# Schemat.net
KiCad netlist of a schematic drawn in EAGLE
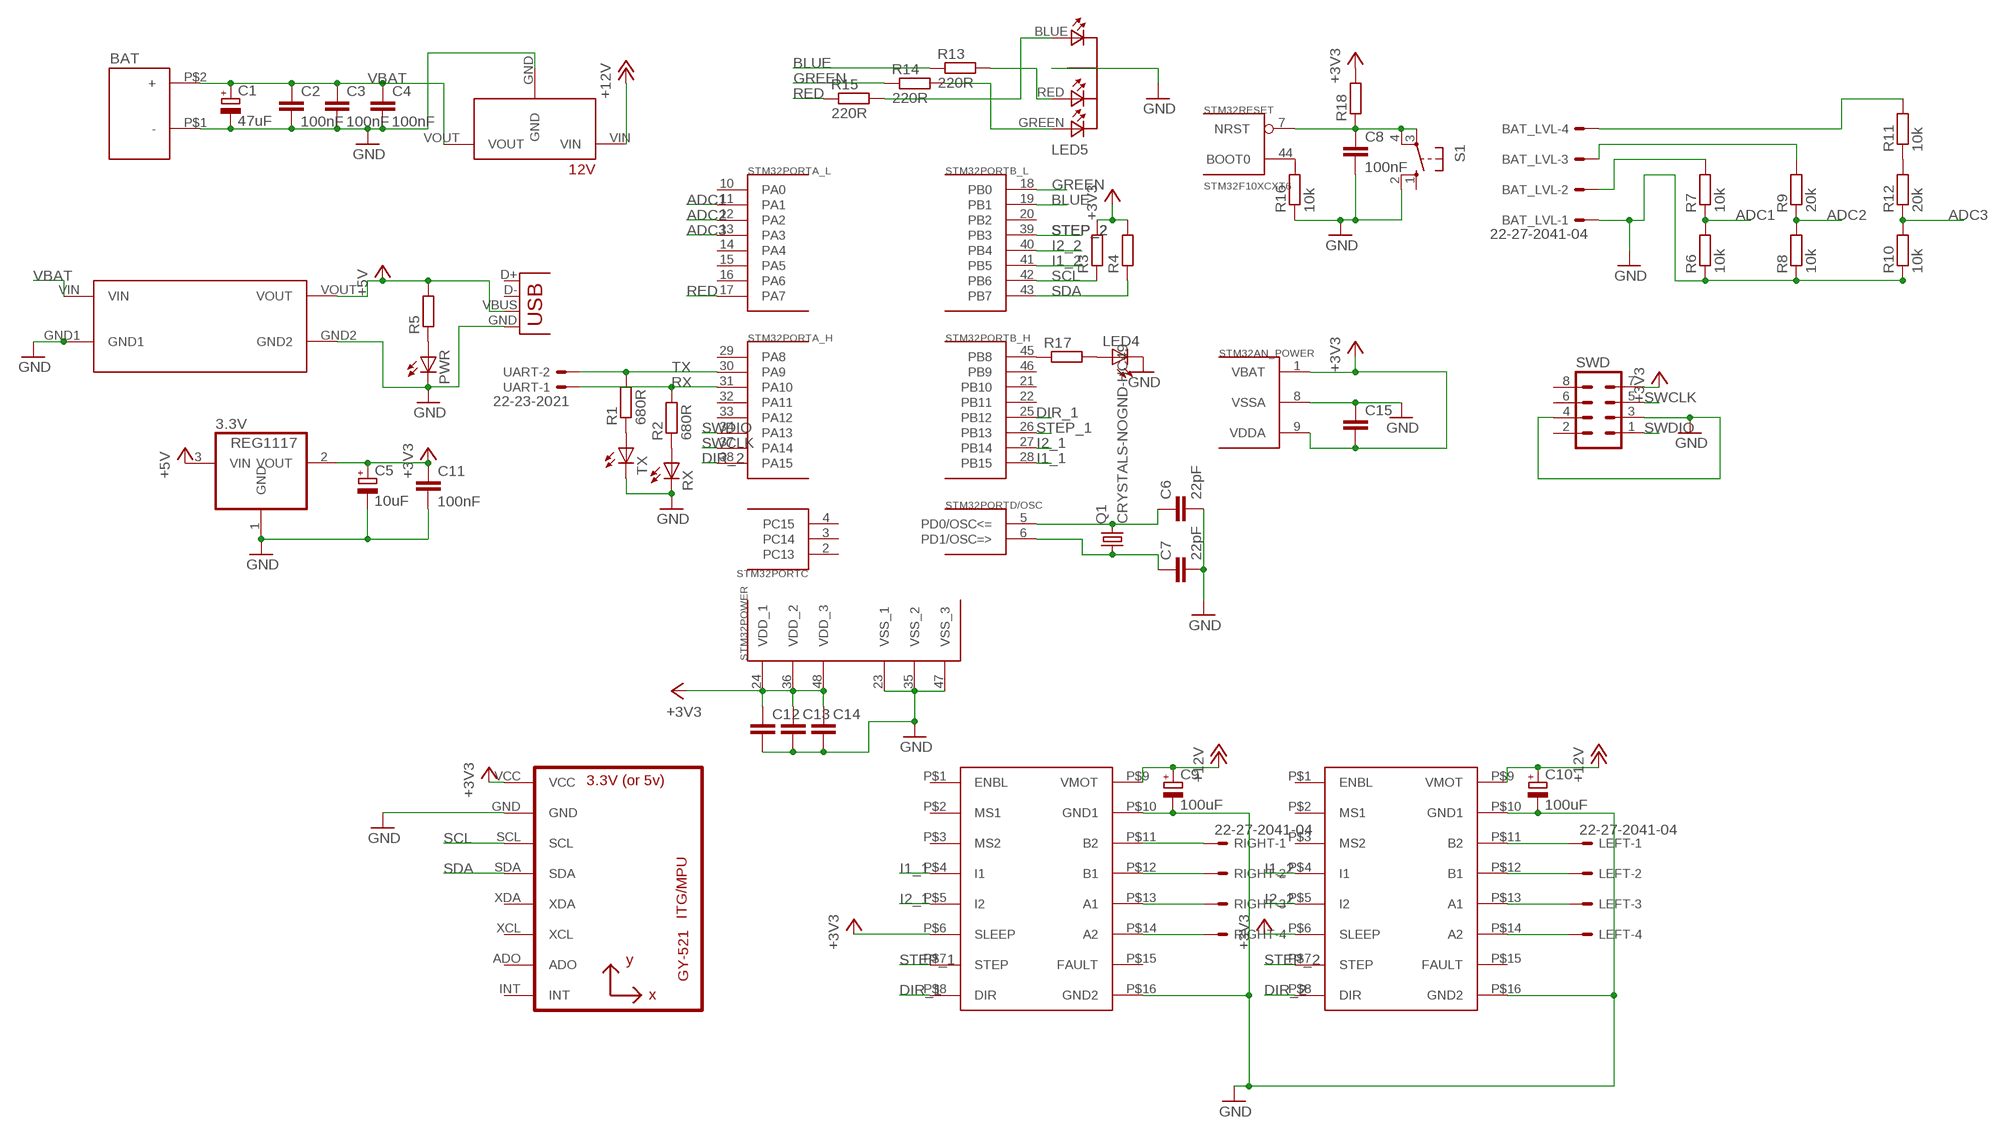
[diagram p0: schematic, sheet 1]

(export (version "E")
  (design (tool "Eeschema 10.0.6"))
  (components
    (comp (ref "3.3V")
      (value "REG1117")
      (footprint "eagle-import:SOT223")
      (libsource (lib "eagle-import") (part "REG1117"))
    )
    (comp (ref "12V")
      (value "12V_VOLTAGE_REGULATOR")
      (footprint "eagle-import:9V_VOLTAGE_REGULATOR")
      (libsource (lib "eagle-import") (part "9V_VOLTAGE_REGULATOR"))
    )
    (comp (ref "BAT")
      (value "DEANS")
      (footprint "eagle-import:DEAN")
      (libsource (lib "eagle-import") (part "DEANS"))
    )
    (comp (ref "BAT_LVL")
      (value "22-27-2041-04")
      (footprint "eagle-import:6410-04")
      (fields (field (name "MF") "MOLEX"))
      (libsource (lib "eagle-import") (part "22-?-0427-2041"))
    )
    (comp (ref "C1")
      (value "47uF")
      (footprint "eagle-import:E2-5")
      (libsource (lib "eagle-import") (part "CPOL-EUE2-5"))
    )
    (comp (ref "C2")
      (value "100nF")
      (footprint "eagle-import:C0603K")
      (libsource (lib "eagle-import") (part "C-EUC0603K"))
    )
    (comp (ref "C3")
      (value "100nF")
      (footprint "eagle-import:C0603K")
      (libsource (lib "eagle-import") (part "C-EUC0603K"))
    )
    (comp (ref "C4")
      (value "100nF")
      (footprint "eagle-import:C0603K")
      (libsource (lib "eagle-import") (part "C-EUC0603K"))
    )
    (comp (ref "C5")
      (value "10uF")
      (footprint "eagle-import:E2-5")
      (libsource (lib "eagle-import") (part "CPOL-EUE2-5"))
    )
    (comp (ref "C6")
      (value "22pF")
      (footprint "eagle-import:C0603K")
      (libsource (lib "eagle-import") (part "C-EUC0603K"))
    )
    (comp (ref "C7")
      (value "22pF")
      (footprint "eagle-import:C0603K")
      (libsource (lib "eagle-import") (part "C-EUC0603K"))
    )
    (comp (ref "C8")
      (value "100nF")
      (footprint "eagle-import:C050-030X075")
      (libsource (lib "eagle-import") (part "C-EU050-030X075"))
    )
    (comp (ref "C9")
      (value "100uF")
      (footprint "eagle-import:E2,5-7")
      (libsource (lib "eagle-import") (part "CPOL-EUE2.5-7"))
    )
    (comp (ref "C10")
      (value "100uF")
      (footprint "eagle-import:E2,5-7")
      (libsource (lib "eagle-import") (part "CPOL-EUE2.5-7"))
    )
    (comp (ref "C11")
      (value "100nF")
      (footprint "eagle-import:C0603")
      (libsource (lib "eagle-import") (part "C-EUC0603"))
    )
    (comp (ref "C12")
      (value "C-EU025-024X044")
      (footprint "eagle-import:C025-024X044")
      (libsource (lib "eagle-import") (part "C-EU025-024X044"))
    )
    (comp (ref "C13")
      (value "C-EU025-024X044")
      (footprint "eagle-import:C025-024X044")
      (libsource (lib "eagle-import") (part "C-EU025-024X044"))
    )
    (comp (ref "C14")
      (value "C-EU025-024X044")
      (footprint "eagle-import:C025-024X044")
      (libsource (lib "eagle-import") (part "C-EU025-024X044"))
    )
    (comp (ref "C15")
      (value "C-EU025-024X044")
      (footprint "eagle-import:C025-024X044")
      (libsource (lib "eagle-import") (part "C-EU025-024X044"))
    )
    (comp (ref "DRV1")
      (value "POLOLU-MP6500")
      (footprint "eagle-import:STEPPER-CARRIER")
      (libsource (lib "eagle-import") (part "POLOLU-MP6500"))
    )
    (comp (ref "DRV2")
      (value "POLOLU-MP6500")
      (footprint "eagle-import:STEPPER-CARRIER")
      (libsource (lib "eagle-import") (part "POLOLU-MP6500"))
    )
    (comp (ref "LED4")
      (value "LED5MM")
      (footprint "eagle-import:LED5MM")
      (libsource (lib "eagle-import") (part "LED5MM"))
    )
    (comp (ref "LED5")
      (value "LED-DIP-3")
      (footprint "eagle-import:DIP-4")
      (libsource (lib "eagle-import") (part "LED-DIP-3"))
    )
    (comp (ref "LEFT")
      (value "22-27-2041-04")
      (footprint "eagle-import:6410-04")
      (fields (field (name "MF") "MOLEX"))
      (libsource (lib "eagle-import") (part "22-?-0427-2041"))
    )
    (comp (ref "PWR")
      (value "LED5MM")
      (footprint "eagle-import:LED5MM")
      (libsource (lib "eagle-import") (part "LED5MM"))
    )
    (comp (ref "Q1")
      (value "CRYSTALS-NOGND-HC49")
      (footprint "eagle-import:HC49")
      (libsource (lib "eagle-import") (part "CRYSTALS-NOGND-HC49"))
    )
    (comp (ref "R1")
      (value "680R")
      (footprint "eagle-import:R0805")
      (libsource (lib "eagle-import") (part "R-EU_R0805"))
    )
    (comp (ref "R2")
      (value "680R")
      (footprint "eagle-import:R0805")
      (libsource (lib "eagle-import") (part "R-EU_R0805"))
    )
    (comp (ref "R3")
      (value "R-EU_R0805")
      (footprint "eagle-import:R0805")
      (libsource (lib "eagle-import") (part "R-EU_R0805"))
    )
    (comp (ref "R4")
      (value "R-EU_R0805")
      (footprint "eagle-import:R0805")
      (libsource (lib "eagle-import") (part "R-EU_R0805"))
    )
    (comp (ref "R5")
      (value "R-EU_R0805")
      (footprint "eagle-import:R0805")
      (libsource (lib "eagle-import") (part "R-EU_R0805"))
    )
    (comp (ref "R6")
      (value "10k")
      (footprint "eagle-import:R0805")
      (libsource (lib "eagle-import") (part "R-EU_R0805"))
    )
    (comp (ref "R7")
      (value "10k")
      (footprint "eagle-import:R0805")
      (libsource (lib "eagle-import") (part "R-EU_R0805"))
    )
    (comp (ref "R8")
      (value "10k")
      (footprint "eagle-import:R0805")
      (libsource (lib "eagle-import") (part "R-EU_R0805"))
    )
    (comp (ref "R9")
      (value "20k")
      (footprint "eagle-import:R0805")
      (libsource (lib "eagle-import") (part "R-EU_R0805"))
    )
    (comp (ref "R10")
      (value "10k")
      (footprint "eagle-import:R0805")
      (libsource (lib "eagle-import") (part "R-EU_R0805"))
    )
    (comp (ref "R11")
      (value "10k")
      (footprint "eagle-import:R0805")
      (libsource (lib "eagle-import") (part "R-EU_R0805"))
    )
    (comp (ref "R12")
      (value "20k")
      (footprint "eagle-import:R0805")
      (libsource (lib "eagle-import") (part "R-EU_R0805"))
    )
    (comp (ref "R13")
      (value "220R")
      (footprint "eagle-import:R0805")
      (libsource (lib "eagle-import") (part "R-EU_R0805"))
    )
    (comp (ref "R14")
      (value "220R")
      (footprint "eagle-import:R0805")
      (libsource (lib "eagle-import") (part "R-EU_R0805"))
    )
    (comp (ref "R15")
      (value "220R")
      (footprint "eagle-import:R0805")
      (libsource (lib "eagle-import") (part "R-EU_R0805"))
    )
    (comp (ref "R16")
      (value "10k")
      (footprint "eagle-import:R0805")
      (libsource (lib "eagle-import") (part "R-EU_R0805"))
    )
    (comp (ref "R17")
      (value "R-EU_R0805")
      (footprint "eagle-import:R0805")
      (libsource (lib "eagle-import") (part "R-EU_R0805"))
    )
    (comp (ref "R18")
      (value "R-EU_R0805")
      (footprint "eagle-import:R0805")
      (libsource (lib "eagle-import") (part "R-EU_R0805"))
    )
    (comp (ref "RIGHT")
      (value "22-27-2041-04")
      (footprint "eagle-import:6410-04")
      (fields (field (name "MF") "MOLEX"))
      (libsource (lib "eagle-import") (part "22-?-0427-2041"))
    )
    (comp (ref "RPI")
      (value "USB-A-H")
      (footprint "eagle-import:USB-A-H")
      (libsource (lib "eagle-import") (part "USB-A-H"))
    )
    (comp (ref "RX")
      (value "LEDSML0603")
      (footprint "eagle-import:SML0603")
      (libsource (lib "eagle-import") (part "LEDSML0603"))
    )
    (comp (ref "S1")
      (value "10-XX")
      (footprint "eagle-import:B3F-10XX")
      (fields (field (name "MPN") "B3F-1000"))
      (libsource (lib "eagle-import") (part "10-XX"))
    )
    (comp (ref "STM32")
      (value "STM32F10XCXT6")
      (footprint "eagle-import:TQFP48")
      (libsource (lib "eagle-import") (part "STM32F10XCXT6"))
    )
    (comp (ref "SWD")
      (value "MA04-2")
      (footprint "eagle-import:MA04-2")
      (libsource (lib "eagle-import") (part "MA04-2"))
    )
    (comp (ref "TX")
      (value "LEDSML0603")
      (footprint "eagle-import:SML0603")
      (libsource (lib "eagle-import") (part "LEDSML0603"))
    )
    (comp (ref "U$1")
      (value "DC-DC")
      (footprint "eagle-import:DC-DC")
      (libsource (lib "eagle-import") (part "DC-DC"))
    )
    (comp (ref "U1")
      (value "GY-521MPU6050")
      (footprint "eagle-import:GY-521")
      (libsource (lib "eagle-import") (part "GY-521MPU6050"))
    )
    (comp (ref "UART")
      (value "22-23-2021")
      (footprint "eagle-import:22-23-2021")
      (fields (field (name "MF") "MOLEX"))
      (libsource (lib "eagle-import") (part "22-23-2021"))
    )
  )
  (nets
    (net (code "1") (name "+3V3") (class "Default")
      (node (ref "3.3V") (pin "2") (pinfunction "VOUT_2") (pintype "output"))
      (node (ref "C11") (pin "1") (pinfunction "1_1") (pintype "passive"))
      (node (ref "C12") (pin "1") (pinfunction "1_1") (pintype "passive"))
      (node (ref "C13") (pin "1") (pinfunction "1_1") (pintype "passive"))
      (node (ref "C14") (pin "1") (pinfunction "1_1") (pintype "passive"))
      (node (ref "C15") (pin "2") (pinfunction "2_2") (pintype "passive"))
      (node (ref "C5") (pin "+") (pinfunction "+_+") (pintype "passive"))
      (node (ref "DRV1") (pin "P$6") (pinfunction "SLEEP_P$6") (pintype "bidirectional"))
      (node (ref "DRV2") (pin "P$6") (pinfunction "SLEEP_P$6") (pintype "bidirectional"))
      (node (ref "R18") (pin "2") (pinfunction "2_2") (pintype "passive"))
      (node (ref "R3") (pin "2") (pinfunction "2_2") (pintype "passive"))
      (node (ref "R4") (pin "2") (pinfunction "2_2") (pintype "passive"))
      (node (ref "STM32") (pin "1") (pinfunction "VBAT_1") (pintype "power_in"))
      (node (ref "STM32") (pin "24") (pinfunction "VDD_1_24") (pintype "power_in"))
      (node (ref "STM32") (pin "36") (pinfunction "VDD_2_36") (pintype "power_in"))
      (node (ref "STM32") (pin "48") (pinfunction "VDD_3_48") (pintype "power_in"))
      (node (ref "STM32") (pin "9") (pinfunction "VDDA_9") (pintype "power_in"))
      (node (ref "SWD") (pin "7") (pinfunction "7_7") (pintype "passive"))
      (node (ref "U1") (pin "VCC") (pinfunction "VCC_VCC") (pintype "bidirectional"))
    )
    (net (code "2") (name "+5V") (class "Default")
      (node (ref "3.3V") (pin "3") (pinfunction "VIN_3") (pintype "input"))
      (node (ref "R5") (pin "2") (pinfunction "2_2") (pintype "passive"))
      (node (ref "RPI") (pin "VBUS") (pinfunction "VBUS_VBUS") (pintype "bidirectional"))
      (node (ref "U$1") (pin "VOUT") (pinfunction "VOUT_VOUT") (pintype "bidirectional"))
    )
    (net (code "3") (name "+12V") (class "Default")
      (node (ref "12V") (pin "VIN") (pinfunction "VIN_VIN") (pintype "bidirectional"))
      (node (ref "C10") (pin "+") (pinfunction "+_+") (pintype "passive"))
      (node (ref "C9") (pin "+") (pinfunction "+_+") (pintype "passive"))
      (node (ref "DRV1") (pin "P$9") (pinfunction "VMOT_P$9") (pintype "bidirectional"))
      (node (ref "DRV2") (pin "P$9") (pinfunction "VMOT_P$9") (pintype "bidirectional"))
    )
    (net (code "4") (name "/ADC1") (class "Default")
      (node (ref "R6") (pin "2") (pinfunction "2_2") (pintype "passive"))
      (node (ref "R7") (pin "1") (pinfunction "1_1") (pintype "passive"))
      (node (ref "STM32") (pin "11") (pinfunction "PA1_11") (pintype "bidirectional"))
    )
    (net (code "5") (name "/ADC2") (class "Default")
      (node (ref "R8") (pin "2") (pinfunction "2_2") (pintype "passive"))
      (node (ref "R9") (pin "1") (pinfunction "1_1") (pintype "passive"))
      (node (ref "STM32") (pin "12") (pinfunction "PA2_12") (pintype "bidirectional"))
    )
    (net (code "6") (name "/ADC3") (class "Default")
      (node (ref "R10") (pin "2") (pinfunction "2_2") (pintype "passive"))
      (node (ref "R12") (pin "1") (pinfunction "1_1") (pintype "passive"))
      (node (ref "STM32") (pin "13") (pinfunction "PA3_13") (pintype "bidirectional"))
    )
    (net (code "7") (name "/BLUE") (class "Default")
      (node (ref "R13") (pin "1") (pinfunction "1_1") (pintype "passive"))
      (node (ref "STM32") (pin "19") (pinfunction "PB1_19") (pintype "bidirectional"))
    )
    (net (code "8") (name "/DIR_1") (class "Default")
      (node (ref "DRV1") (pin "P$8") (pinfunction "DIR_P$8") (pintype "bidirectional"))
      (node (ref "STM32") (pin "25") (pinfunction "PB12_25") (pintype "bidirectional"))
    )
    (net (code "9") (name "/DIR_2") (class "Default")
      (node (ref "DRV2") (pin "P$8") (pinfunction "DIR_P$8") (pintype "bidirectional"))
      (node (ref "STM32") (pin "38") (pinfunction "PA15_38") (pintype "bidirectional"))
    )
    (net (code "10") (name "/GREEN") (class "Default")
      (node (ref "R14") (pin "1") (pinfunction "1_1") (pintype "passive"))
      (node (ref "STM32") (pin "18") (pinfunction "PB0_18") (pintype "bidirectional"))
    )
    (net (code "11") (name "/I1_1") (class "Default")
      (node (ref "DRV1") (pin "P$4") (pinfunction "I1_P$4") (pintype "bidirectional"))
      (node (ref "STM32") (pin "28") (pinfunction "PB15_28") (pintype "bidirectional"))
    )
    (net (code "12") (name "/I1_2") (class "Default")
      (node (ref "DRV2") (pin "P$4") (pinfunction "I1_P$4") (pintype "bidirectional"))
      (node (ref "STM32") (pin "41") (pinfunction "PB5_41") (pintype "bidirectional"))
    )
    (net (code "13") (name "/I2_1") (class "Default")
      (node (ref "DRV1") (pin "P$5") (pinfunction "I2_P$5") (pintype "bidirectional"))
      (node (ref "STM32") (pin "27") (pinfunction "PB14_27") (pintype "bidirectional"))
    )
    (net (code "14") (name "/I2_2") (class "Default")
      (node (ref "DRV2") (pin "P$5") (pinfunction "I2_P$5") (pintype "bidirectional"))
      (node (ref "STM32") (pin "40") (pinfunction "PB4_40") (pintype "bidirectional"))
    )
    (net (code "15") (name "/RED") (class "Default")
      (node (ref "R15") (pin "1") (pinfunction "1_1") (pintype "passive"))
      (node (ref "STM32") (pin "17") (pinfunction "PA7_17") (pintype "bidirectional"))
    )
    (net (code "16") (name "/RX") (class "Default")
      (node (ref "R2") (pin "2") (pinfunction "2_2") (pintype "passive"))
      (node (ref "STM32") (pin "31") (pinfunction "PA10_31") (pintype "bidirectional"))
      (node (ref "UART") (pin "1") (pinfunction "S_1") (pintype "passive"))
    )
    (net (code "17") (name "/SCL") (class "Default")
      (node (ref "R3") (pin "1") (pinfunction "1_1") (pintype "passive"))
      (node (ref "STM32") (pin "42") (pinfunction "PB6_42") (pintype "bidirectional"))
      (node (ref "U1") (pin "SCL") (pinfunction "SCL_SCL") (pintype "bidirectional"))
    )
    (net (code "18") (name "/SDA") (class "Default")
      (node (ref "R4") (pin "1") (pinfunction "1_1") (pintype "passive"))
      (node (ref "STM32") (pin "43") (pinfunction "PB7_43") (pintype "bidirectional"))
      (node (ref "U1") (pin "SDA") (pinfunction "SDA_SDA") (pintype "bidirectional"))
    )
    (net (code "19") (name "/STEP_1") (class "Default")
      (node (ref "DRV1") (pin "P$7") (pinfunction "STEP_P$7") (pintype "bidirectional"))
      (node (ref "STM32") (pin "26") (pinfunction "PB13_26") (pintype "bidirectional"))
    )
    (net (code "20") (name "/STEP_2") (class "Default")
      (node (ref "DRV2") (pin "P$7") (pinfunction "STEP_P$7") (pintype "bidirectional"))
      (node (ref "STM32") (pin "39") (pinfunction "PB3_39") (pintype "bidirectional"))
    )
    (net (code "21") (name "/SWCLK") (class "Default")
      (node (ref "STM32") (pin "37") (pinfunction "PA14_37") (pintype "bidirectional"))
      (node (ref "SWD") (pin "5") (pinfunction "5_5") (pintype "passive"))
    )
    (net (code "22") (name "/SWDIO") (class "Default")
      (node (ref "STM32") (pin "34") (pinfunction "PA13_34") (pintype "bidirectional"))
      (node (ref "SWD") (pin "1") (pinfunction "1_1") (pintype "passive"))
    )
    (net (code "23") (name "/TX") (class "Default")
      (node (ref "R1") (pin "2") (pinfunction "2_2") (pintype "passive"))
      (node (ref "STM32") (pin "30") (pinfunction "PA9_30") (pintype "bidirectional"))
      (node (ref "UART") (pin "2") (pinfunction "S_2") (pintype "passive"))
    )
    (net (code "24") (name "/VBAT") (class "Default")
      (node (ref "12V") (pin "VOUT") (pinfunction "VOUT_VOUT") (pintype "bidirectional"))
      (node (ref "BAT") (pin "P$2") (pinfunction "+_P$2") (pintype "bidirectional"))
      (node (ref "C1") (pin "+") (pinfunction "+_+") (pintype "passive"))
      (node (ref "C2") (pin "1") (pinfunction "1_1") (pintype "passive"))
      (node (ref "C3") (pin "1") (pinfunction "1_1") (pintype "passive"))
      (node (ref "C4") (pin "1") (pinfunction "1_1") (pintype "passive"))
      (node (ref "U$1") (pin "VIN") (pinfunction "VIN_VIN") (pintype "bidirectional"))
    )
    (net (code "25") (name "GND") (class "Default")
      (node (ref "12V") (pin "GND") (pinfunction "GND_GND") (pintype "bidirectional"))
      (node (ref "3.3V") (pin "1") (pinfunction "GND_1") (pintype "power_in"))
      (node (ref "BAT") (pin "P$1") (pinfunction "-_P$1") (pintype "bidirectional"))
      (node (ref "BAT_LVL") (pin "1") (pinfunction "S_1") (pintype "passive"))
      (node (ref "C1") (pin "-") (pinfunction "-_-") (pintype "passive"))
      (node (ref "C10") (pin "-") (pinfunction "-_-") (pintype "passive"))
      (node (ref "C11") (pin "2") (pinfunction "2_2") (pintype "passive"))
      (node (ref "C12") (pin "2") (pinfunction "2_2") (pintype "passive"))
      (node (ref "C13") (pin "2") (pinfunction "2_2") (pintype "passive"))
      (node (ref "C14") (pin "2") (pinfunction "2_2") (pintype "passive"))
      (node (ref "C15") (pin "1") (pinfunction "1_1") (pintype "passive"))
      (node (ref "C2") (pin "2") (pinfunction "2_2") (pintype "passive"))
      (node (ref "C3") (pin "2") (pinfunction "2_2") (pintype "passive"))
      (node (ref "C4") (pin "2") (pinfunction "2_2") (pintype "passive"))
      (node (ref "C5") (pin "-") (pinfunction "-_-") (pintype "passive"))
      (node (ref "C6") (pin "2") (pinfunction "2_2") (pintype "passive"))
      (node (ref "C7") (pin "2") (pinfunction "2_2") (pintype "passive"))
      (node (ref "C8") (pin "2") (pinfunction "2_2") (pintype "passive"))
      (node (ref "C9") (pin "-") (pinfunction "-_-") (pintype "passive"))
      (node (ref "DRV1") (pin "P$10") (pinfunction "GND1_P$10") (pintype "bidirectional"))
      (node (ref "DRV1") (pin "P$16") (pinfunction "GND2_P$16") (pintype "bidirectional"))
      (node (ref "DRV2") (pin "P$10") (pinfunction "GND1_P$10") (pintype "bidirectional"))
      (node (ref "DRV2") (pin "P$16") (pinfunction "GND2_P$16") (pintype "bidirectional"))
      (node (ref "LED4") (pin "K") (pinfunction "C_K") (pintype "passive"))
      (node (ref "LED5") (pin "COMMON_CATHODE") (pinfunction "COM-CATHODE_COMMON_CATHODE") (pintype "passive"))
      (node (ref "PWR") (pin "K") (pinfunction "C_K") (pintype "passive"))
      (node (ref "R10") (pin "1") (pinfunction "1_1") (pintype "passive"))
      (node (ref "R16") (pin "1") (pinfunction "1_1") (pintype "passive"))
      (node (ref "R6") (pin "1") (pinfunction "1_1") (pintype "passive"))
      (node (ref "R8") (pin "1") (pinfunction "1_1") (pintype "passive"))
      (node (ref "RPI") (pin "GND") (pinfunction "GND_GND") (pintype "bidirectional"))
      (node (ref "RX") (pin "C") (pinfunction "C_C") (pintype "passive"))
      (node (ref "S1") (pin "2") (pinfunction "S1_2") (pintype "passive"))
      (node (ref "STM32") (pin "23") (pinfunction "VSS_1_23") (pintype "power_in"))
      (node (ref "STM32") (pin "35") (pinfunction "VSS_2_35") (pintype "power_in"))
      (node (ref "STM32") (pin "47") (pinfunction "VSS_3_47") (pintype "power_in"))
      (node (ref "STM32") (pin "8") (pinfunction "VSSA_8") (pintype "power_in"))
      (node (ref "SWD") (pin "3") (pinfunction "3_3") (pintype "passive"))
      (node (ref "SWD") (pin "4") (pinfunction "4_4") (pintype "passive"))
      (node (ref "TX") (pin "C") (pinfunction "C_C") (pintype "passive"))
      (node (ref "U$1") (pin "GND1") (pinfunction "GND1_GND1") (pintype "bidirectional"))
      (node (ref "U$1") (pin "GND2") (pinfunction "GND2_GND2") (pintype "bidirectional"))
      (node (ref "U1") (pin "GND") (pinfunction "GND_GND") (pintype "bidirectional"))
    )
    (net (code "26") (name "Net-(BAT_LVLB-S)") (class "Default")
      (node (ref "BAT_LVL") (pin "2") (pinfunction "S_2") (pintype "passive"))
      (node (ref "R7") (pin "2") (pinfunction "2_2") (pintype "passive"))
    )
    (net (code "27") (name "Net-(BAT_LVLC-S)") (class "Default")
      (node (ref "BAT_LVL") (pin "3") (pinfunction "S_3") (pintype "passive"))
      (node (ref "R9") (pin "2") (pinfunction "2_2") (pintype "passive"))
    )
    (net (code "28") (name "Net-(BAT_LVLD-S)") (class "Default")
      (node (ref "BAT_LVL") (pin "4") (pinfunction "S_4") (pintype "passive"))
      (node (ref "R11") (pin "2") (pinfunction "2_2") (pintype "passive"))
    )
    (net (code "29") (name "Net-(DRV1-A1)") (class "Default")
      (node (ref "DRV1") (pin "P$13") (pinfunction "A1_P$13") (pintype "bidirectional"))
      (node (ref "RIGHT") (pin "3") (pinfunction "S_3") (pintype "passive"))
    )
    (net (code "30") (name "Net-(DRV1-A2)") (class "Default")
      (node (ref "DRV1") (pin "P$14") (pinfunction "A2_P$14") (pintype "bidirectional"))
      (node (ref "RIGHT") (pin "4") (pinfunction "S_4") (pintype "passive"))
    )
    (net (code "31") (name "Net-(DRV1-B1)") (class "Default")
      (node (ref "DRV1") (pin "P$12") (pinfunction "B1_P$12") (pintype "bidirectional"))
      (node (ref "RIGHT") (pin "2") (pinfunction "S_2") (pintype "passive"))
    )
    (net (code "32") (name "Net-(DRV1-B2)") (class "Default")
      (node (ref "DRV1") (pin "P$11") (pinfunction "B2_P$11") (pintype "bidirectional"))
      (node (ref "RIGHT") (pin "1") (pinfunction "S_1") (pintype "passive"))
    )
    (net (code "33") (name "Net-(DRV2-A1)") (class "Default")
      (node (ref "DRV2") (pin "P$13") (pinfunction "A1_P$13") (pintype "bidirectional"))
      (node (ref "LEFT") (pin "3") (pinfunction "S_3") (pintype "passive"))
    )
    (net (code "34") (name "Net-(DRV2-A2)") (class "Default")
      (node (ref "DRV2") (pin "P$14") (pinfunction "A2_P$14") (pintype "bidirectional"))
      (node (ref "LEFT") (pin "4") (pinfunction "S_4") (pintype "passive"))
    )
    (net (code "35") (name "Net-(DRV2-B1)") (class "Default")
      (node (ref "DRV2") (pin "P$12") (pinfunction "B1_P$12") (pintype "bidirectional"))
      (node (ref "LEFT") (pin "2") (pinfunction "S_2") (pintype "passive"))
    )
    (net (code "36") (name "Net-(DRV2-B2)") (class "Default")
      (node (ref "DRV2") (pin "P$11") (pinfunction "B2_P$11") (pintype "bidirectional"))
      (node (ref "LEFT") (pin "1") (pinfunction "S_1") (pintype "passive"))
    )
    (net (code "37") (name "Net-(LED4-PadA)") (class "Default")
      (node (ref "LED4") (pin "A") (pinfunction "A_A") (pintype "passive"))
      (node (ref "R17") (pin "2") (pinfunction "2_2") (pintype "passive"))
    )
    (net (code "38") (name "Net-(LED5-PadBLUE)") (class "Default")
      (node (ref "LED5") (pin "BLUE") (pinfunction "BLUE_BLUE") (pintype "passive"))
      (node (ref "R15") (pin "2") (pinfunction "2_2") (pintype "passive"))
    )
    (net (code "39") (name "Net-(LED5-PadGREEN)") (class "Default")
      (node (ref "LED5") (pin "GREEN") (pinfunction "GREEN_GREEN") (pintype "passive"))
      (node (ref "R14") (pin "2") (pinfunction "2_2") (pintype "passive"))
    )
    (net (code "40") (name "Net-(LED5-PadRED)") (class "Default")
      (node (ref "LED5") (pin "RED") (pinfunction "RED_RED") (pintype "passive"))
      (node (ref "R13") (pin "2") (pinfunction "2_2") (pintype "passive"))
    )
    (net (code "41") (name "Net-(PWR-PadA)") (class "Default")
      (node (ref "PWR") (pin "A") (pinfunction "A_A") (pintype "passive"))
      (node (ref "R5") (pin "1") (pinfunction "1_1") (pintype "passive"))
    )
    (net (code "42") (name "Net-(R1-Pad1)") (class "Default")
      (node (ref "R1") (pin "1") (pinfunction "1_1") (pintype "passive"))
      (node (ref "TX") (pin "A") (pinfunction "A_A") (pintype "passive"))
    )
    (net (code "43") (name "Net-(R2-Pad1)") (class "Default")
      (node (ref "R2") (pin "1") (pinfunction "1_1") (pintype "passive"))
      (node (ref "RX") (pin "A") (pinfunction "A_A") (pintype "passive"))
    )
    (net (code "44") (name "Net-(R11-Pad1)") (class "Default")
      (node (ref "R11") (pin "1") (pinfunction "1_1") (pintype "passive"))
      (node (ref "R12") (pin "2") (pinfunction "2_2") (pintype "passive"))
    )
    (net (code "45") (name "Net-(S1-P)") (class "Default")
      (node (ref "C8") (pin "1") (pinfunction "1_1") (pintype "passive"))
      (node (ref "R18") (pin "1") (pinfunction "1_1") (pintype "passive"))
      (node (ref "S1") (pin "3") (pinfunction "P_3") (pintype "passive"))
      (node (ref "S1") (pin "4") (pinfunction "P1_4") (pintype "passive"))
      (node (ref "STM32") (pin "7") (pinfunction "NRST_7") (pintype "input"))
    )
    (net (code "46") (name "Net-(STM32D-PB8)") (class "Default")
      (node (ref "R17") (pin "1") (pinfunction "1_1") (pintype "passive"))
      (node (ref "STM32") (pin "45") (pinfunction "PB8_45") (pintype "bidirectional"))
    )
    (net (code "47") (name "Net-(STM32G-PD0{slash}OSC<=)") (class "Default")
      (node (ref "C6") (pin "1") (pinfunction "1_1") (pintype "passive"))
      (node (ref "Q1") (pin "2") (pinfunction "2_2") (pintype "passive"))
      (node (ref "STM32") (pin "5") (pinfunction "PD0/OSC<=_5") (pintype "bidirectional"))
    )
    (net (code "48") (name "Net-(STM32G-PD1{slash}OSC=>)") (class "Default")
      (node (ref "C7") (pin "1") (pinfunction "1_1") (pintype "passive"))
      (node (ref "Q1") (pin "1") (pinfunction "1_1") (pintype "passive"))
      (node (ref "STM32") (pin "6") (pinfunction "PD1/OSC=>_6") (pintype "bidirectional"))
    )
    (net (code "49") (name "Net-(STM32I-BOOT0)") (class "Default")
      (node (ref "R16") (pin "2") (pinfunction "2_2") (pintype "passive"))
      (node (ref "STM32") (pin "44") (pinfunction "BOOT0_44") (pintype "input"))
    )
    (net (code "50") (name "unconnected-(DRV1-ENBL-PadP$1)") (class "Default")
      (node (ref "DRV1") (pin "P$1") (pinfunction "ENBL_P$1") (pintype "bidirectional"))
    )
    (net (code "51") (name "unconnected-(DRV1-FAULT-PadP$15)") (class "Default")
      (node (ref "DRV1") (pin "P$15") (pinfunction "FAULT_P$15") (pintype "bidirectional"))
    )
    (net (code "52") (name "unconnected-(DRV1-MS1-PadP$2)") (class "Default")
      (node (ref "DRV1") (pin "P$2") (pinfunction "MS1_P$2") (pintype "bidirectional"))
    )
    (net (code "53") (name "unconnected-(DRV1-MS2-PadP$3)") (class "Default")
      (node (ref "DRV1") (pin "P$3") (pinfunction "MS2_P$3") (pintype "bidirectional"))
    )
    (net (code "54") (name "unconnected-(DRV2-ENBL-PadP$1)") (class "Default")
      (node (ref "DRV2") (pin "P$1") (pinfunction "ENBL_P$1") (pintype "bidirectional"))
    )
    (net (code "55") (name "unconnected-(DRV2-FAULT-PadP$15)") (class "Default")
      (node (ref "DRV2") (pin "P$15") (pinfunction "FAULT_P$15") (pintype "bidirectional"))
    )
    (net (code "56") (name "unconnected-(DRV2-MS1-PadP$2)") (class "Default")
      (node (ref "DRV2") (pin "P$2") (pinfunction "MS1_P$2") (pintype "bidirectional"))
    )
    (net (code "57") (name "unconnected-(DRV2-MS2-PadP$3)") (class "Default")
      (node (ref "DRV2") (pin "P$3") (pinfunction "MS2_P$3") (pintype "bidirectional"))
    )
    (net (code "58") (name "unconnected-(RPI-PadD+)") (class "Default")
      (node (ref "RPI") (pin "D+") (pinfunction "D+_D+") (pintype "bidirectional"))
    )
    (net (code "59") (name "unconnected-(RPI-PadD-)") (class "Default")
      (node (ref "RPI") (pin "D-") (pinfunction "D-_D-") (pintype "bidirectional"))
    )
    (net (code "60") (name "unconnected-(S1-S-Pad1)") (class "Default")
      (node (ref "S1") (pin "1") (pinfunction "S_1") (pintype "passive"))
    )
    (net (code "61") (name "unconnected-(STM32B-PA8-Pad29)") (class "Default")
      (node (ref "STM32") (pin "29") (pinfunction "PA8_29") (pintype "bidirectional"))
    )
    (net (code "62") (name "unconnected-(STM32B-PA11-Pad32)") (class "Default")
      (node (ref "STM32") (pin "32") (pinfunction "PA11_32") (pintype "bidirectional"))
    )
    (net (code "63") (name "unconnected-(STM32B-PA12-Pad33)") (class "Default")
      (node (ref "STM32") (pin "33") (pinfunction "PA12_33") (pintype "bidirectional"))
    )
    (net (code "64") (name "unconnected-(STM32C-PA0-Pad10)") (class "Default")
      (node (ref "STM32") (pin "10") (pinfunction "PA0_10") (pintype "bidirectional"))
    )
    (net (code "65") (name "unconnected-(STM32C-PA4-Pad14)") (class "Default")
      (node (ref "STM32") (pin "14") (pinfunction "PA4_14") (pintype "bidirectional"))
    )
    (net (code "66") (name "unconnected-(STM32C-PA5-Pad15)") (class "Default")
      (node (ref "STM32") (pin "15") (pinfunction "PA5_15") (pintype "bidirectional"))
    )
    (net (code "67") (name "unconnected-(STM32C-PA6-Pad16)") (class "Default")
      (node (ref "STM32") (pin "16") (pinfunction "PA6_16") (pintype "bidirectional"))
    )
    (net (code "68") (name "unconnected-(STM32D-PB9-Pad46)") (class "Default")
      (node (ref "STM32") (pin "46") (pinfunction "PB9_46") (pintype "bidirectional"))
    )
    (net (code "69") (name "unconnected-(STM32D-PB10-Pad21)") (class "Default")
      (node (ref "STM32") (pin "21") (pinfunction "PB10_21") (pintype "bidirectional"))
    )
    (net (code "70") (name "unconnected-(STM32D-PB11-Pad22)") (class "Default")
      (node (ref "STM32") (pin "22") (pinfunction "PB11_22") (pintype "bidirectional"))
    )
    (net (code "71") (name "unconnected-(STM32E-PB2-Pad20)") (class "Default")
      (node (ref "STM32") (pin "20") (pinfunction "PB2_20") (pintype "bidirectional"))
    )
    (net (code "72") (name "unconnected-(STM32F-PC13-Pad2)") (class "Default")
      (node (ref "STM32") (pin "2") (pinfunction "PC13_2") (pintype "bidirectional"))
    )
    (net (code "73") (name "unconnected-(STM32F-PC14-Pad3)") (class "Default")
      (node (ref "STM32") (pin "3") (pinfunction "PC14_3") (pintype "bidirectional"))
    )
    (net (code "74") (name "unconnected-(STM32F-PC15-Pad4)") (class "Default")
      (node (ref "STM32") (pin "4") (pinfunction "PC15_4") (pintype "bidirectional"))
    )
    (net (code "75") (name "unconnected-(SWD-Pad2)") (class "Default")
      (node (ref "SWD") (pin "2") (pinfunction "2_2") (pintype "passive"))
    )
    (net (code "76") (name "unconnected-(SWD-Pad6)") (class "Default")
      (node (ref "SWD") (pin "6") (pinfunction "6_6") (pintype "passive"))
    )
    (net (code "77") (name "unconnected-(SWD-Pad8)") (class "Default")
      (node (ref "SWD") (pin "8") (pinfunction "8_8") (pintype "passive"))
    )
    (net (code "78") (name "unconnected-(U1-PadADO)") (class "Default")
      (node (ref "U1") (pin "ADO") (pinfunction "ADO_ADO") (pintype "bidirectional"))
    )
    (net (code "79") (name "unconnected-(U1-PadINT)") (class "Default")
      (node (ref "U1") (pin "INT") (pinfunction "INT_INT") (pintype "bidirectional"))
    )
    (net (code "80") (name "unconnected-(U1-PadXCL)") (class "Default")
      (node (ref "U1") (pin "XCL") (pinfunction "XCL_XCL") (pintype "bidirectional"))
    )
    (net (code "81") (name "unconnected-(U1-PadXDA)") (class "Default")
      (node (ref "U1") (pin "XDA") (pinfunction "XDA_XDA") (pintype "bidirectional"))
    )
  )
)
